# RF_Attenuator.net
KiCad netlist of a schematic drawn in Altium Designer
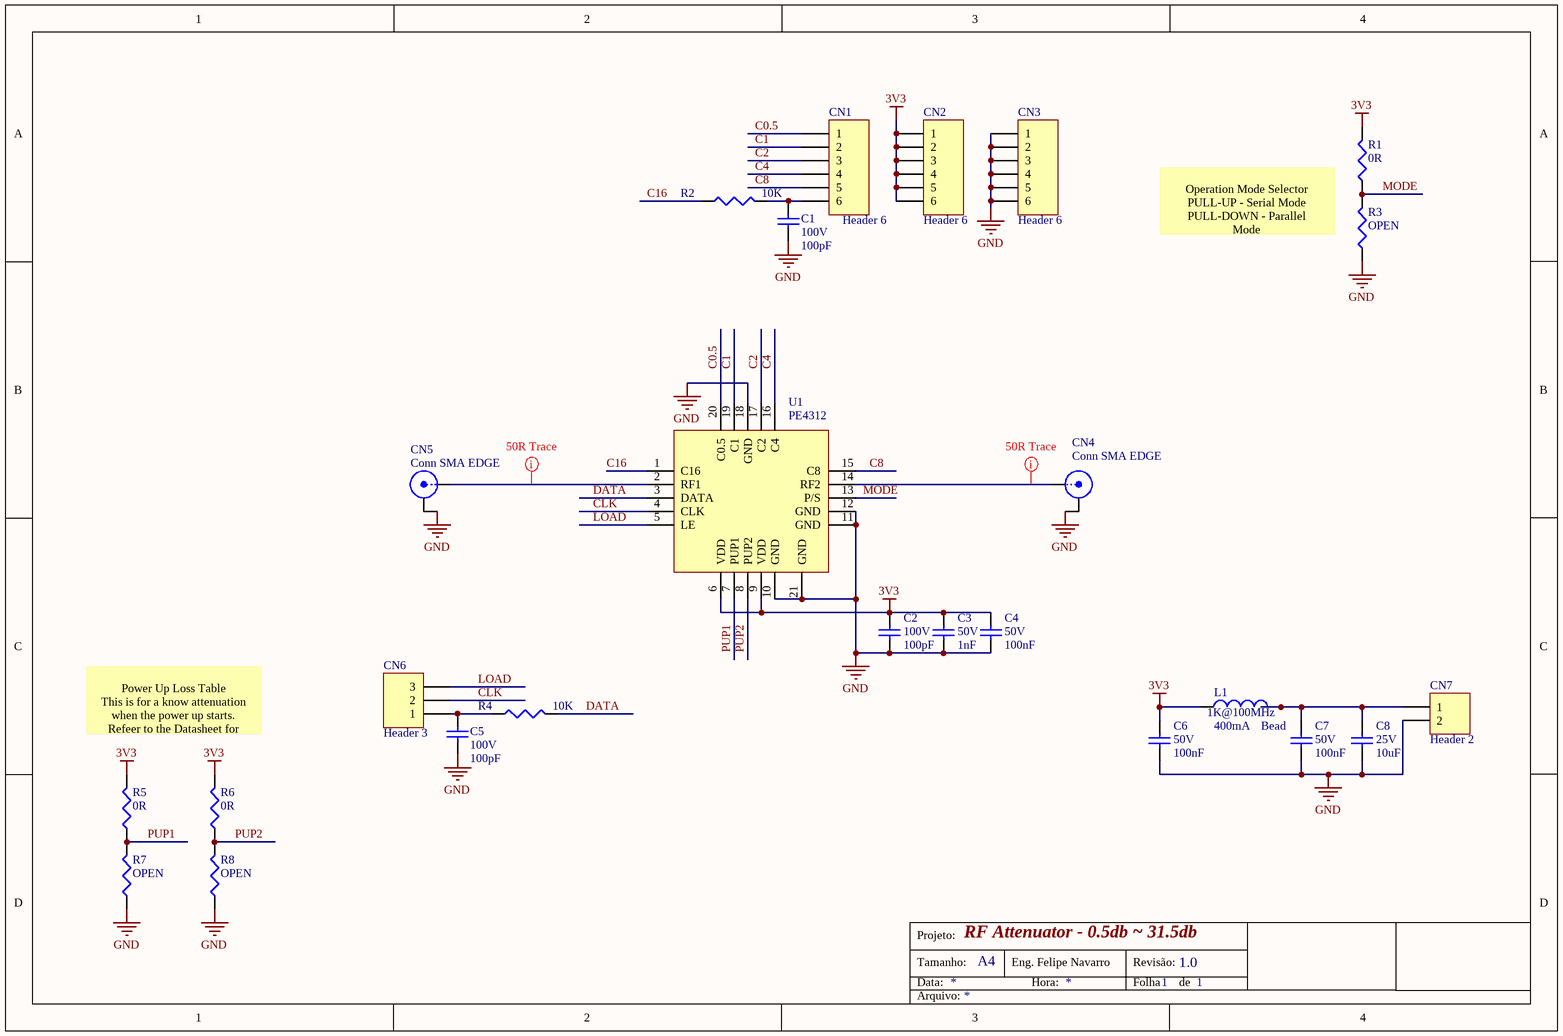
[diagram p0: RF_Attenuator.SchDoc]

(export (version "E")
  (design (tool "Eeschema 10.0.6"))
  (components
    (comp (ref "C1")
      (value "100pF")
      (footprint "CC0603")
      (description "Capacitor (Semiconductor SIM Model)")
      (fields (field (name "TENSÃO") "100V") (field (name "Comment") "Capacitor Cerâmico"))
      (libsource (lib "NavarroCAP") (part "Cap 100pF 100V 0603 NP0"))
    )
    (comp (ref "C2")
      (value "100pF")
      (footprint "CC0603")
      (description "Capacitor (Semiconductor SIM Model)")
      (fields (field (name "TENSÃO") "100V") (field (name "Comment") "Capacitor Cerâmico"))
      (libsource (lib "NavarroCAP") (part "Cap 100pF 100V 0603 NP0"))
    )
    (comp (ref "C3")
      (value "1nF")
      (footprint "CC0603")
      (description "Capacitor (Semiconductor SIM Model)")
      (fields (field (name "TENSÃO") "50V") (field (name "Comment") "Capacitor Cerâmico"))
      (libsource (lib "NavarroCAP") (part "Cap 1nF 50V 0603 NP0"))
    )
    (comp (ref "C4")
      (value "100nF")
      (footprint "CC0603")
      (description "Capacitor (Semiconductor SIM Model)")
      (fields (field (name "TENSÃO") "50V") (field (name "Comment") "Capacitor Cerâmico"))
      (libsource (lib "NavarroCAP") (part "Cap 100nF 50V 0603 X7R"))
    )
    (comp (ref "C5")
      (value "100pF")
      (footprint "CC0603")
      (description "Capacitor (Semiconductor SIM Model)")
      (fields (field (name "TENSÃO") "100V") (field (name "Comment") "Capacitor Cerâmico"))
      (libsource (lib "NavarroCAP") (part "Cap 100pF 100V 0603 NP0"))
    )
    (comp (ref "C6")
      (value "100nF")
      (footprint "CC0603")
      (description "Capacitor (Semiconductor SIM Model)")
      (fields (field (name "TENSÃO") "50V") (field (name "Comment") "Capacitor Cerâmico"))
      (libsource (lib "NavarroCAP") (part "Cap 100nF 50V 0603 X7R"))
    )
    (comp (ref "C7")
      (value "100nF")
      (footprint "CC0603")
      (description "Capacitor (Semiconductor SIM Model)")
      (fields (field (name "TENSÃO") "50V") (field (name "Comment") "Capacitor Cerâmico"))
      (libsource (lib "NavarroCAP") (part "Cap 100nF 50V 0603 X7R"))
    )
    (comp (ref "C8")
      (value "10uF")
      (footprint "CC0805")
      (description "Capacitor (Semiconductor SIM Model)")
      (fields (field (name "TENSÃO") "25V") (field (name "Comment") "Capacitor Cerâmico"))
      (libsource (lib "NavarroCAP") (part "Cap 10uF 25V 0805 X5R"))
    )
    (comp (ref "CN1")
      (value "Header 6")
      (footprint "CONN HDR1X6")
      (description "Header, 6-Pin")
      (libsource (lib "NavarroCON") (part "Header 6"))
    )
    (comp (ref "CN2")
      (value "Header 6")
      (footprint "CONN HDR1X6")
      (description "Header, 6-Pin")
      (libsource (lib "NavarroCON") (part "Header 6"))
    )
    (comp (ref "CN3")
      (value "Header 6")
      (footprint "CONN HDR1X6")
      (description "Header, 6-Pin")
      (libsource (lib "NavarroCON") (part "Header 6"))
    )
    (comp (ref "CN4")
      (value "Conn SMA EDGE")
      (footprint "CONN SMA EDGE MOUNT")
      (description "Conector SMA")
      (libsource (lib "NavarroCON") (part "Conn SMA EDGE"))
    )
    (comp (ref "CN5")
      (value "Conn SMA EDGE")
      (footprint "CONN SMA EDGE MOUNT")
      (description "Conector SMA")
      (libsource (lib "NavarroCON") (part "Conn SMA EDGE"))
    )
    (comp (ref "CN6")
      (value "Header 3")
      (footprint "CONN HDR1X3")
      (description "Header, 3-Pin")
      (libsource (lib "NavarroCON") (part "Header 3"))
    )
    (comp (ref "CN7")
      (value "Header 2")
      (footprint "CONN HDR1X2")
      (description "Header, 2-Pin")
      (libsource (lib "NavarroCON") (part "Header 2"))
    )
    (comp (ref "L1")
      (value "Bead")
      (footprint "CC0603")
      (fields (field (name "CORRENTE") "400mA") (field (name "ALTIUM_VALUE") "1K@100MHz"))
      (libsource (lib "NavarroIND") (part "Bd 1K@100MHz 0603 400mA"))
    )
    (comp (ref "R1")
      (value "0R")
      (footprint "CC0603")
      (description "Resistor")
      (libsource (lib "NavarroRES") (part "Res 0R 0603 1/10W"))
    )
    (comp (ref "R2")
      (value "10K")
      (footprint "CC0603")
      (description "Resistor")
      (libsource (lib "NavarroRES") (part "Res 10K 1% 0603 1/10W"))
    )
    (comp (ref "R3")
      (value "OPEN")
      (footprint "CC0603")
      (description "Resistor")
      (fields (field (name "Comment") "Resistor Open"))
      (libsource (lib "NavarroRES") (part "Res Open 0603"))
    )
    (comp (ref "R4")
      (value "10K")
      (footprint "CC0603")
      (description "Resistor")
      (libsource (lib "NavarroRES") (part "Res 10K 1% 0603 1/10W"))
    )
    (comp (ref "R5")
      (value "0R")
      (footprint "CC0603")
      (description "Resistor")
      (libsource (lib "NavarroRES") (part "Res 0R 0603 1/10W"))
    )
    (comp (ref "R6")
      (value "0R")
      (footprint "CC0603")
      (description "Resistor")
      (libsource (lib "NavarroRES") (part "Res 0R 0603 1/10W"))
    )
    (comp (ref "R7")
      (value "OPEN")
      (footprint "CC0603")
      (description "Resistor")
      (fields (field (name "Comment") "Resistor Open"))
      (libsource (lib "NavarroRES") (part "Res Open 0603"))
    )
    (comp (ref "R8")
      (value "OPEN")
      (footprint "CC0603")
      (description "Resistor")
      (fields (field (name "Comment") "Resistor Open"))
      (libsource (lib "NavarroRES") (part "Res Open 0603"))
    )
    (comp (ref "U1")
      (value "PE4312")
      (footprint "QFN4X4-20N")
      (description "UltraCMOS® RF Digital Step Attenuator 6-bit, 31.5 dB, 1 MHz–4 GHz")
      (libsource (lib "Navarro") (part "PE4312"))
    )
  )
  (nets
    (net (code "1") (name "/C0.5") (class "Default")
      (node (ref "CN1") (pin "1") (pinfunction "1_1") (pintype "passive"))
      (node (ref "U1") (pin "20") (pinfunction "C0.5_20") (pintype "passive"))
    )
    (net (code "2") (name "/C1") (class "Default")
      (node (ref "CN1") (pin "2") (pinfunction "2_2") (pintype "passive"))
      (node (ref "U1") (pin "19") (pinfunction "C1_19") (pintype "passive"))
    )
    (net (code "3") (name "/C2") (class "Default")
      (node (ref "CN1") (pin "3") (pinfunction "3_3") (pintype "passive"))
      (node (ref "U1") (pin "17") (pinfunction "C2_17") (pintype "passive"))
    )
    (net (code "4") (name "/C4") (class "Default")
      (node (ref "CN1") (pin "4") (pinfunction "4_4") (pintype "passive"))
      (node (ref "U1") (pin "16") (pinfunction "C4_16") (pintype "passive"))
    )
    (net (code "5") (name "/C8") (class "Default")
      (node (ref "CN1") (pin "5") (pinfunction "5_5") (pintype "passive"))
      (node (ref "U1") (pin "15") (pinfunction "C8_15") (pintype "passive"))
    )
    (net (code "6") (name "/C16") (class "Default")
      (node (ref "R2") (pin "1") (pinfunction "1_1") (pintype "passive"))
      (node (ref "U1") (pin "1") (pinfunction "C16_1") (pintype "passive"))
    )
    (net (code "7") (name "/CLK") (class "Default")
      (node (ref "CN6") (pin "2") (pinfunction "2_2") (pintype "passive"))
      (node (ref "U1") (pin "4") (pinfunction "CLK_4") (pintype "passive"))
    )
    (net (code "8") (name "/DATA") (class "Default")
      (node (ref "R4") (pin "2") (pinfunction "2_2") (pintype "passive"))
      (node (ref "U1") (pin "3") (pinfunction "DATA_3") (pintype "passive"))
    )
    (net (code "9") (name "/LOAD") (class "Default")
      (node (ref "CN6") (pin "3") (pinfunction "3_3") (pintype "passive"))
      (node (ref "U1") (pin "5") (pinfunction "LE_5") (pintype "passive"))
    )
    (net (code "10") (name "/MODE") (class "Default")
      (node (ref "R1") (pin "1") (pinfunction "1_1") (pintype "passive"))
      (node (ref "R3") (pin "2") (pinfunction "2_2") (pintype "passive"))
      (node (ref "U1") (pin "13") (pinfunction "P/S_13") (pintype "passive"))
    )
    (net (code "11") (name "/PUP1") (class "Default")
      (node (ref "R5") (pin "1") (pinfunction "1_1") (pintype "passive"))
      (node (ref "R7") (pin "2") (pinfunction "2_2") (pintype "passive"))
      (node (ref "U1") (pin "7") (pinfunction "PUP1_7") (pintype "passive"))
    )
    (net (code "12") (name "/PUP2") (class "Default")
      (node (ref "R6") (pin "1") (pinfunction "1_1") (pintype "passive"))
      (node (ref "R8") (pin "2") (pinfunction "2_2") (pintype "passive"))
      (node (ref "U1") (pin "8") (pinfunction "PUP2_8") (pintype "passive"))
    )
    (net (code "13") (name "3V3") (class "Default")
      (node (ref "C2") (pin "2") (pinfunction "2_2") (pintype "passive"))
      (node (ref "C3") (pin "2") (pinfunction "2_2") (pintype "passive"))
      (node (ref "C4") (pin "2") (pinfunction "2_2") (pintype "passive"))
      (node (ref "C6") (pin "2") (pinfunction "2_2") (pintype "passive"))
      (node (ref "CN2") (pin "1") (pinfunction "1_1") (pintype "passive"))
      (node (ref "CN2") (pin "2") (pinfunction "2_2") (pintype "passive"))
      (node (ref "CN2") (pin "3") (pinfunction "3_3") (pintype "passive"))
      (node (ref "CN2") (pin "4") (pinfunction "4_4") (pintype "passive"))
      (node (ref "CN2") (pin "5") (pinfunction "5_5") (pintype "passive"))
      (node (ref "CN2") (pin "6") (pinfunction "6_6") (pintype "passive"))
      (node (ref "L1") (pin "1") (pinfunction "1_1") (pintype "passive"))
      (node (ref "R1") (pin "2") (pinfunction "2_2") (pintype "passive"))
      (node (ref "R5") (pin "2") (pinfunction "2_2") (pintype "passive"))
      (node (ref "R6") (pin "2") (pinfunction "2_2") (pintype "passive"))
      (node (ref "U1") (pin "6") (pinfunction "VDD_6") (pintype "passive"))
      (node (ref "U1") (pin "9") (pinfunction "VDD_9") (pintype "passive"))
    )
    (net (code "14") (name "GND") (class "Default")
      (node (ref "C1") (pin "1") (pinfunction "1_1") (pintype "passive"))
      (node (ref "C2") (pin "1") (pinfunction "1_1") (pintype "passive"))
      (node (ref "C3") (pin "1") (pinfunction "1_1") (pintype "passive"))
      (node (ref "C4") (pin "1") (pinfunction "1_1") (pintype "passive"))
      (node (ref "C5") (pin "1") (pinfunction "1_1") (pintype "passive"))
      (node (ref "C6") (pin "1") (pinfunction "1_1") (pintype "passive"))
      (node (ref "C7") (pin "1") (pinfunction "1_1") (pintype "passive"))
      (node (ref "C8") (pin "1") (pinfunction "1_1") (pintype "passive"))
      (node (ref "CN3") (pin "1") (pinfunction "1_1") (pintype "passive"))
      (node (ref "CN3") (pin "2") (pinfunction "2_2") (pintype "passive"))
      (node (ref "CN3") (pin "3") (pinfunction "3_3") (pintype "passive"))
      (node (ref "CN3") (pin "4") (pinfunction "4_4") (pintype "passive"))
      (node (ref "CN3") (pin "5") (pinfunction "5_5") (pintype "passive"))
      (node (ref "CN3") (pin "6") (pinfunction "6_6") (pintype "passive"))
      (node (ref "CN4") (pin "G") (pinfunction "G_G") (pintype "passive"))
      (node (ref "CN5") (pin "G") (pinfunction "G_G") (pintype "passive"))
      (node (ref "CN7") (pin "2") (pinfunction "2_2") (pintype "passive"))
      (node (ref "R3") (pin "1") (pinfunction "1_1") (pintype "passive"))
      (node (ref "R7") (pin "1") (pinfunction "1_1") (pintype "passive"))
      (node (ref "R8") (pin "1") (pinfunction "1_1") (pintype "passive"))
      (node (ref "U1") (pin "10") (pinfunction "GND_10") (pintype "passive"))
      (node (ref "U1") (pin "11") (pinfunction "GND_11") (pintype "passive"))
      (node (ref "U1") (pin "12") (pinfunction "GND_12") (pintype "passive"))
      (node (ref "U1") (pin "18") (pinfunction "GND_18") (pintype "passive"))
      (node (ref "U1") (pin "21") (pinfunction "GND_21") (pintype "passive"))
    )
    (net (code "15") (name "Net-(C1-Pad2)") (class "Default")
      (node (ref "C1") (pin "2") (pinfunction "2_2") (pintype "passive"))
      (node (ref "CN1") (pin "6") (pinfunction "6_6") (pintype "passive"))
      (node (ref "R2") (pin "2") (pinfunction "2_2") (pintype "passive"))
    )
    (net (code "16") (name "Net-(C5-Pad2)") (class "Default")
      (node (ref "C5") (pin "2") (pinfunction "2_2") (pintype "passive"))
      (node (ref "CN6") (pin "1") (pinfunction "1_1") (pintype "passive"))
      (node (ref "R4") (pin "1") (pinfunction "1_1") (pintype "passive"))
    )
    (net (code "17") (name "Net-(C7-Pad2)") (class "Default")
      (node (ref "C7") (pin "2") (pinfunction "2_2") (pintype "passive"))
      (node (ref "C8") (pin "2") (pinfunction "2_2") (pintype "passive"))
      (node (ref "CN7") (pin "1") (pinfunction "1_1") (pintype "passive"))
      (node (ref "L1") (pin "2") (pinfunction "2_2") (pintype "passive"))
    )
    (net (code "18") (name "Net-(U1-RF1)") (class "Default")
      (node (ref "CN5") (pin "S") (pinfunction "S_S") (pintype "passive"))
      (node (ref "U1") (pin "2") (pinfunction "RF1_2") (pintype "passive"))
    )
    (net (code "19") (name "Net-(U1-RF2)") (class "Default")
      (node (ref "CN4") (pin "S") (pinfunction "S_S") (pintype "passive"))
      (node (ref "U1") (pin "14") (pinfunction "RF2_14") (pintype "passive"))
    )
  )
)
